# encoders.net
KiCad netlist of a schematic drawn in Altium Designer
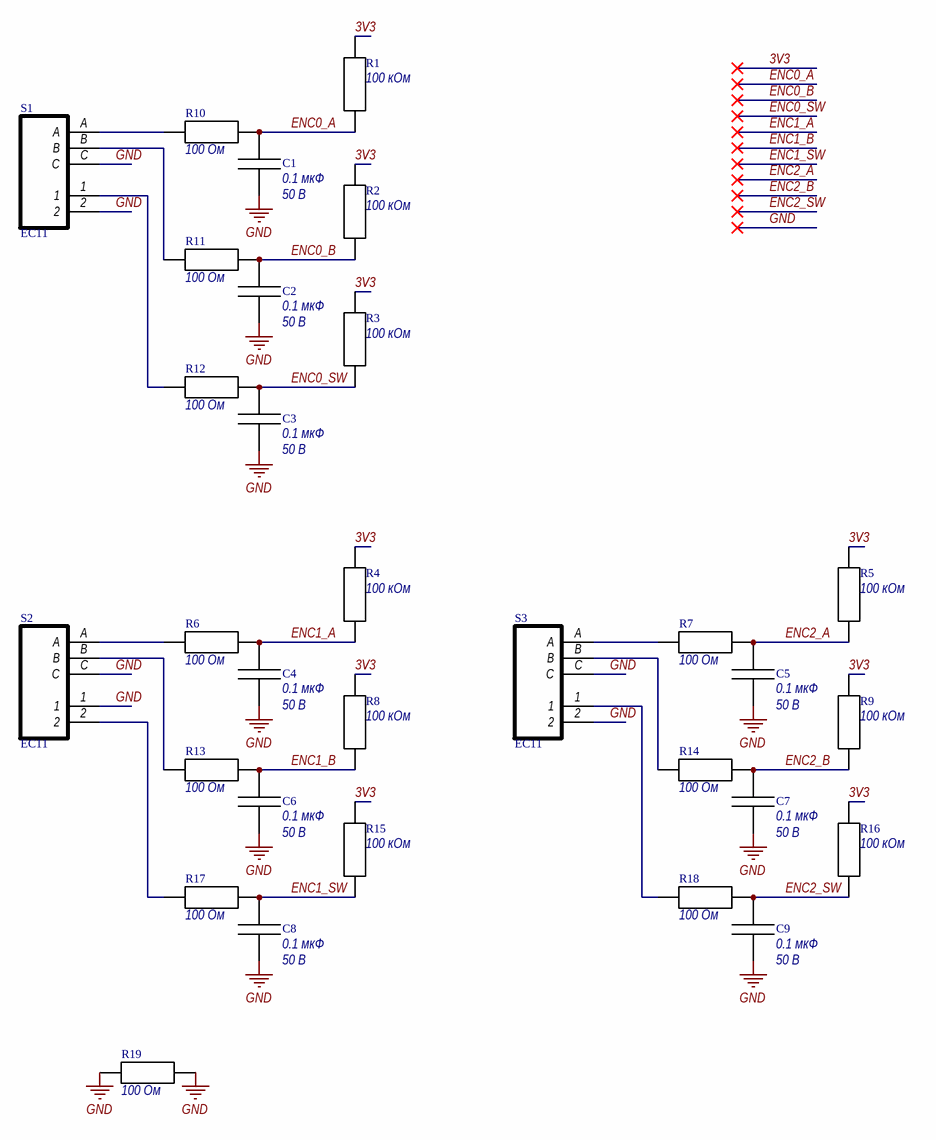
[diagram p0: encoders.SchDoc]

(export (version "E")
  (design (tool "Eeschema 10.0.6"))
  (components
    (comp (ref "C1")
      (value "0.1 мкФ")
      (footprint "0805-CAP")
      (description "Конденсатор керамический, 0.1 мкФ, X7R, 50 В, точность 10%, 0805")
      (fields (field (name "VOLTAGE") "50 В") (field (name "Comment") "GRM21BR71H104K"))
      (libsource (lib "Altium Vault") (part "CMP-0544-A.1"))
    )
    (comp (ref "C2")
      (value "0.1 мкФ")
      (footprint "0805-CAP")
      (description "Конденсатор керамический, 0.1 мкФ, X7R, 50 В, точность 10%, 0805")
      (fields (field (name "VOLTAGE") "50 В") (field (name "Comment") "GRM21BR71H104K"))
      (libsource (lib "Altium Vault") (part "CMP-0544-A.1"))
    )
    (comp (ref "C3")
      (value "0.1 мкФ")
      (footprint "0805-CAP")
      (description "Конденсатор керамический, 0.1 мкФ, X7R, 50 В, точность 10%, 0805")
      (fields (field (name "VOLTAGE") "50 В") (field (name "Comment") "GRM21BR71H104K"))
      (libsource (lib "Altium Vault") (part "CMP-0544-A.1"))
    )
    (comp (ref "C4")
      (value "0.1 мкФ")
      (footprint "0805-CAP")
      (description "Конденсатор керамический, 0.1 мкФ, X7R, 50 В, точность 10%, 0805")
      (fields (field (name "VOLTAGE") "50 В") (field (name "Comment") "GRM21BR71H104K"))
      (libsource (lib "Altium Vault") (part "CMP-0544-A.1"))
    )
    (comp (ref "C5")
      (value "0.1 мкФ")
      (footprint "0805-CAP")
      (description "Конденсатор керамический, 0.1 мкФ, X7R, 50 В, точность 10%, 0805")
      (fields (field (name "VOLTAGE") "50 В") (field (name "Comment") "GRM21BR71H104K"))
      (libsource (lib "Altium Vault") (part "CMP-0544-A.1"))
    )
    (comp (ref "C6")
      (value "0.1 мкФ")
      (footprint "0805-CAP")
      (description "Конденсатор керамический, 0.1 мкФ, X7R, 50 В, точность 10%, 0805")
      (fields (field (name "VOLTAGE") "50 В") (field (name "Comment") "GRM21BR71H104K"))
      (libsource (lib "Altium Vault") (part "CMP-0544-A.1"))
    )
    (comp (ref "C7")
      (value "0.1 мкФ")
      (footprint "0805-CAP")
      (description "Конденсатор керамический, 0.1 мкФ, X7R, 50 В, точность 10%, 0805")
      (fields (field (name "VOLTAGE") "50 В") (field (name "Comment") "GRM21BR71H104K"))
      (libsource (lib "Altium Vault") (part "CMP-0544-A.1"))
    )
    (comp (ref "C8")
      (value "0.1 мкФ")
      (footprint "0805-CAP")
      (description "Конденсатор керамический, 0.1 мкФ, X7R, 50 В, точность 10%, 0805")
      (fields (field (name "VOLTAGE") "50 В") (field (name "Comment") "GRM21BR71H104K"))
      (libsource (lib "Altium Vault") (part "CMP-0544-A.1"))
    )
    (comp (ref "C9")
      (value "0.1 мкФ")
      (footprint "0805-CAP")
      (description "Конденсатор керамический, 0.1 мкФ, X7R, 50 В, точность 10%, 0805")
      (fields (field (name "VOLTAGE") "50 В") (field (name "Comment") "GRM21BR71H104K"))
      (libsource (lib "Altium Vault") (part "CMP-0544-A.1"))
    )
    (comp (ref "R1")
      (value "100 кОм")
      (footprint "0805-RES")
      (description "Резистор, 100 кОм, 0.125 Вт, точность 1%, 0805")
      (fields (field (name "MANUFACTURER") "YAGEO") (field (name "Comment") "RC0805FR-07100KL"))
      (libsource (lib "Altium Vault") (part "CMP-0672-A.2"))
    )
    (comp (ref "R2")
      (value "100 кОм")
      (footprint "0805-RES")
      (description "Резистор, 100 кОм, 0.125 Вт, точность 1%, 0805")
      (fields (field (name "MANUFACTURER") "YAGEO") (field (name "Comment") "RC0805FR-07100KL"))
      (libsource (lib "Altium Vault") (part "CMP-0672-A.2"))
    )
    (comp (ref "R3")
      (value "100 кОм")
      (footprint "0805-RES")
      (description "Резистор, 100 кОм, 0.125 Вт, точность 1%, 0805")
      (fields (field (name "MANUFACTURER") "YAGEO") (field (name "Comment") "RC0805FR-07100KL"))
      (libsource (lib "Altium Vault") (part "CMP-0672-A.2"))
    )
    (comp (ref "R4")
      (value "100 кОм")
      (footprint "0805-RES")
      (description "Резистор, 100 кОм, 0.125 Вт, точность 1%, 0805")
      (fields (field (name "MANUFACTURER") "YAGEO") (field (name "Comment") "RC0805FR-07100KL"))
      (libsource (lib "Altium Vault") (part "CMP-0672-A.2"))
    )
    (comp (ref "R5")
      (value "100 кОм")
      (footprint "0805-RES")
      (description "Резистор, 100 кОм, 0.125 Вт, точность 1%, 0805")
      (fields (field (name "MANUFACTURER") "YAGEO") (field (name "Comment") "RC0805FR-07100KL"))
      (libsource (lib "Altium Vault") (part "CMP-0672-A.2"))
    )
    (comp (ref "R6")
      (value "100 Ом")
      (footprint "0805-RES")
      (description "Резистор, 100 Ом, 0.125 Вт, точность 1%, 0805")
      (fields (field (name "MANUFACTURER") "YAGEO") (field (name "Comment") "RC0805FR-07100RL"))
      (libsource (lib "Altium Vault") (part "CMP-0727-A.1"))
    )
    (comp (ref "R7")
      (value "100 Ом")
      (footprint "0805-RES")
      (description "Резистор, 100 Ом, 0.125 Вт, точность 1%, 0805")
      (fields (field (name "MANUFACTURER") "YAGEO") (field (name "Comment") "RC0805FR-07100RL"))
      (libsource (lib "Altium Vault") (part "CMP-0727-A.1"))
    )
    (comp (ref "R8")
      (value "100 кОм")
      (footprint "0805-RES")
      (description "Резистор, 100 кОм, 0.125 Вт, точность 1%, 0805")
      (fields (field (name "MANUFACTURER") "YAGEO") (field (name "Comment") "RC0805FR-07100KL"))
      (libsource (lib "Altium Vault") (part "CMP-0672-A.2"))
    )
    (comp (ref "R9")
      (value "100 кОм")
      (footprint "0805-RES")
      (description "Резистор, 100 кОм, 0.125 Вт, точность 1%, 0805")
      (fields (field (name "MANUFACTURER") "YAGEO") (field (name "Comment") "RC0805FR-07100KL"))
      (libsource (lib "Altium Vault") (part "CMP-0672-A.2"))
    )
    (comp (ref "R10")
      (value "100 Ом")
      (footprint "0805-RES")
      (description "Резистор, 100 Ом, 0.125 Вт, точность 1%, 0805")
      (fields (field (name "MANUFACTURER") "YAGEO") (field (name "Comment") "RC0805FR-07100RL"))
      (libsource (lib "Altium Vault") (part "CMP-0727-A.1"))
    )
    (comp (ref "R11")
      (value "100 Ом")
      (footprint "0805-RES")
      (description "Резистор, 100 Ом, 0.125 Вт, точность 1%, 0805")
      (fields (field (name "MANUFACTURER") "YAGEO") (field (name "Comment") "RC0805FR-07100RL"))
      (libsource (lib "Altium Vault") (part "CMP-0727-A.1"))
    )
    (comp (ref "R12")
      (value "100 Ом")
      (footprint "0805-RES")
      (description "Резистор, 100 Ом, 0.125 Вт, точность 1%, 0805")
      (fields (field (name "MANUFACTURER") "YAGEO") (field (name "Comment") "RC0805FR-07100RL"))
      (libsource (lib "Altium Vault") (part "CMP-0727-A.1"))
    )
    (comp (ref "R13")
      (value "100 Ом")
      (footprint "0805-RES")
      (description "Резистор, 100 Ом, 0.125 Вт, точность 1%, 0805")
      (fields (field (name "MANUFACTURER") "YAGEO") (field (name "Comment") "RC0805FR-07100RL"))
      (libsource (lib "Altium Vault") (part "CMP-0727-A.1"))
    )
    (comp (ref "R14")
      (value "100 Ом")
      (footprint "0805-RES")
      (description "Резистор, 100 Ом, 0.125 Вт, точность 1%, 0805")
      (fields (field (name "MANUFACTURER") "YAGEO") (field (name "Comment") "RC0805FR-07100RL"))
      (libsource (lib "Altium Vault") (part "CMP-0727-A.1"))
    )
    (comp (ref "R15")
      (value "100 кОм")
      (footprint "0805-RES")
      (description "Резистор, 100 кОм, 0.125 Вт, точность 1%, 0805")
      (fields (field (name "MANUFACTURER") "YAGEO") (field (name "Comment") "RC0805FR-07100KL"))
      (libsource (lib "Altium Vault") (part "CMP-0672-A.2"))
    )
    (comp (ref "R16")
      (value "100 кОм")
      (footprint "0805-RES")
      (description "Резистор, 100 кОм, 0.125 Вт, точность 1%, 0805")
      (fields (field (name "MANUFACTURER") "YAGEO") (field (name "Comment") "RC0805FR-07100KL"))
      (libsource (lib "Altium Vault") (part "CMP-0672-A.2"))
    )
    (comp (ref "R17")
      (value "100 Ом")
      (footprint "0805-RES")
      (description "Резистор, 100 Ом, 0.125 Вт, точность 1%, 0805")
      (fields (field (name "MANUFACTURER") "YAGEO") (field (name "Comment") "RC0805FR-07100RL"))
      (libsource (lib "Altium Vault") (part "CMP-0727-A.1"))
    )
    (comp (ref "R18")
      (value "100 Ом")
      (footprint "0805-RES")
      (description "Резистор, 100 Ом, 0.125 Вт, точность 1%, 0805")
      (fields (field (name "MANUFACTURER") "YAGEO") (field (name "Comment") "RC0805FR-07100RL"))
      (libsource (lib "Altium Vault") (part "CMP-0727-A.1"))
    )
    (comp (ref "R19")
      (value "100 Ом")
      (footprint "0805-RES")
      (description "Резистор, 100 Ом, 0.125 Вт, точность 1%, 0805")
      (fields (field (name "MANUFACTURER") "YAGEO") (field (name "Comment") "RC0805FR-07100RL"))
      (libsource (lib "Altium Vault") (part "CMP-0727-A.1"))
    )
    (comp (ref "S1")
      (value "EC11")
      (footprint "482020514001")
      (description "Энкодер, с кнопкой, монтаж в отверстия")
      (fields (field (name "MANUFACTURER") "NA"))
      (libsource (lib "Altium Vault") (part "Энкодер с кнопкой"))
    )
    (comp (ref "S2")
      (value "EC11")
      (footprint "482020514001")
      (description "Энкодер, с кнопкой, монтаж в отверстия")
      (fields (field (name "MANUFACTURER") "NA"))
      (libsource (lib "Altium Vault") (part "Энкодер с кнопкой"))
    )
    (comp (ref "S3")
      (value "EC11")
      (footprint "482020514001")
      (description "Энкодер, с кнопкой, монтаж в отверстия")
      (fields (field (name "MANUFACTURER") "NA"))
      (libsource (lib "Altium Vault") (part "Энкодер с кнопкой"))
    )
  )
  (nets
    (net (code "1") (name "/3V3") (class "Default")
      (node (ref "R1") (pin "2") (pinfunction "2_2") (pintype "passive"))
      (node (ref "R15") (pin "2") (pinfunction "2_2") (pintype "passive"))
      (node (ref "R16") (pin "2") (pinfunction "2_2") (pintype "passive"))
      (node (ref "R2") (pin "2") (pinfunction "2_2") (pintype "passive"))
      (node (ref "R3") (pin "2") (pinfunction "2_2") (pintype "passive"))
      (node (ref "R4") (pin "2") (pinfunction "2_2") (pintype "passive"))
      (node (ref "R5") (pin "2") (pinfunction "2_2") (pintype "passive"))
      (node (ref "R8") (pin "2") (pinfunction "2_2") (pintype "passive"))
      (node (ref "R9") (pin "2") (pinfunction "2_2") (pintype "passive"))
    )
    (net (code "2") (name "/ENC0_A") (class "Default")
      (node (ref "C1") (pin "2") (pinfunction "2_2") (pintype "passive"))
      (node (ref "R1") (pin "1") (pinfunction "1_1") (pintype "passive"))
      (node (ref "R10") (pin "1") (pinfunction "1_1") (pintype "passive"))
    )
    (net (code "3") (name "/ENC0_B") (class "Default")
      (node (ref "C2") (pin "2") (pinfunction "2_2") (pintype "passive"))
      (node (ref "R11") (pin "1") (pinfunction "1_1") (pintype "passive"))
      (node (ref "R2") (pin "1") (pinfunction "1_1") (pintype "passive"))
    )
    (net (code "4") (name "/ENC0_SW") (class "Default")
      (node (ref "C3") (pin "2") (pinfunction "2_2") (pintype "passive"))
      (node (ref "R12") (pin "1") (pinfunction "1_1") (pintype "passive"))
      (node (ref "R3") (pin "1") (pinfunction "1_1") (pintype "passive"))
    )
    (net (code "5") (name "/ENC1_A") (class "Default")
      (node (ref "C4") (pin "2") (pinfunction "2_2") (pintype "passive"))
      (node (ref "R4") (pin "1") (pinfunction "1_1") (pintype "passive"))
      (node (ref "R6") (pin "1") (pinfunction "1_1") (pintype "passive"))
    )
    (net (code "6") (name "/ENC1_B") (class "Default")
      (node (ref "C6") (pin "2") (pinfunction "2_2") (pintype "passive"))
      (node (ref "R13") (pin "1") (pinfunction "1_1") (pintype "passive"))
      (node (ref "R8") (pin "1") (pinfunction "1_1") (pintype "passive"))
    )
    (net (code "7") (name "/ENC1_SW") (class "Default")
      (node (ref "C8") (pin "2") (pinfunction "2_2") (pintype "passive"))
      (node (ref "R15") (pin "1") (pinfunction "1_1") (pintype "passive"))
      (node (ref "R17") (pin "1") (pinfunction "1_1") (pintype "passive"))
    )
    (net (code "8") (name "/ENC2_A") (class "Default")
      (node (ref "C5") (pin "2") (pinfunction "2_2") (pintype "passive"))
      (node (ref "R5") (pin "1") (pinfunction "1_1") (pintype "passive"))
      (node (ref "R7") (pin "1") (pinfunction "1_1") (pintype "passive"))
    )
    (net (code "9") (name "/ENC2_B") (class "Default")
      (node (ref "C7") (pin "2") (pinfunction "2_2") (pintype "passive"))
      (node (ref "R14") (pin "1") (pinfunction "1_1") (pintype "passive"))
      (node (ref "R9") (pin "1") (pinfunction "1_1") (pintype "passive"))
    )
    (net (code "10") (name "/ENC2_SW") (class "Default")
      (node (ref "C9") (pin "2") (pinfunction "2_2") (pintype "passive"))
      (node (ref "R16") (pin "1") (pinfunction "1_1") (pintype "passive"))
      (node (ref "R18") (pin "1") (pinfunction "1_1") (pintype "passive"))
    )
    (net (code "11") (name "GND") (class "Default")
      (node (ref "C1") (pin "1") (pinfunction "1_1") (pintype "passive"))
      (node (ref "C2") (pin "1") (pinfunction "1_1") (pintype "passive"))
      (node (ref "C3") (pin "1") (pinfunction "1_1") (pintype "passive"))
      (node (ref "C4") (pin "1") (pinfunction "1_1") (pintype "passive"))
      (node (ref "C5") (pin "1") (pinfunction "1_1") (pintype "passive"))
      (node (ref "C6") (pin "1") (pinfunction "1_1") (pintype "passive"))
      (node (ref "C7") (pin "1") (pinfunction "1_1") (pintype "passive"))
      (node (ref "C8") (pin "1") (pinfunction "1_1") (pintype "passive"))
      (node (ref "C9") (pin "1") (pinfunction "1_1") (pintype "passive"))
      (node (ref "R19") (pin "1") (pinfunction "1_1") (pintype "passive"))
      (node (ref "R19") (pin "2") (pinfunction "2_2") (pintype "passive"))
      (node (ref "S1") (pin "2") (pinfunction "2_2") (pintype "passive"))
      (node (ref "S1") (pin "C") (pinfunction "C_C") (pintype "passive"))
      (node (ref "S2") (pin "1") (pinfunction "1_1") (pintype "passive"))
      (node (ref "S2") (pin "C") (pinfunction "C_C") (pintype "passive"))
      (node (ref "S3") (pin "2") (pinfunction "2_2") (pintype "passive"))
      (node (ref "S3") (pin "C") (pinfunction "C_C") (pintype "passive"))
    )
    (net (code "12") (name "Net-(R6-Pad2)") (class "Default")
      (node (ref "R6") (pin "2") (pinfunction "2_2") (pintype "passive"))
      (node (ref "S2") (pin "A") (pinfunction "A_A") (pintype "passive"))
    )
    (net (code "13") (name "Net-(R7-Pad2)") (class "Default")
      (node (ref "R7") (pin "2") (pinfunction "2_2") (pintype "passive"))
      (node (ref "S3") (pin "A") (pinfunction "A_A") (pintype "passive"))
    )
    (net (code "14") (name "Net-(R10-Pad2)") (class "Default")
      (node (ref "R10") (pin "2") (pinfunction "2_2") (pintype "passive"))
      (node (ref "S1") (pin "A") (pinfunction "A_A") (pintype "passive"))
    )
    (net (code "15") (name "Net-(R11-Pad2)") (class "Default")
      (node (ref "R11") (pin "2") (pinfunction "2_2") (pintype "passive"))
      (node (ref "S1") (pin "B") (pinfunction "B_B") (pintype "passive"))
    )
    (net (code "16") (name "Net-(R12-Pad2)") (class "Default")
      (node (ref "R12") (pin "2") (pinfunction "2_2") (pintype "passive"))
      (node (ref "S1") (pin "1") (pinfunction "1_1") (pintype "passive"))
    )
    (net (code "17") (name "Net-(R13-Pad2)") (class "Default")
      (node (ref "R13") (pin "2") (pinfunction "2_2") (pintype "passive"))
      (node (ref "S2") (pin "B") (pinfunction "B_B") (pintype "passive"))
    )
    (net (code "18") (name "Net-(R14-Pad2)") (class "Default")
      (node (ref "R14") (pin "2") (pinfunction "2_2") (pintype "passive"))
      (node (ref "S3") (pin "B") (pinfunction "B_B") (pintype "passive"))
    )
    (net (code "19") (name "Net-(R17-Pad2)") (class "Default")
      (node (ref "R17") (pin "2") (pinfunction "2_2") (pintype "passive"))
      (node (ref "S2") (pin "2") (pinfunction "2_2") (pintype "passive"))
    )
    (net (code "20") (name "Net-(R18-Pad2)") (class "Default")
      (node (ref "R18") (pin "2") (pinfunction "2_2") (pintype "passive"))
      (node (ref "S3") (pin "1") (pinfunction "1_1") (pintype "passive"))
    )
  )
)
